# tempeh_Hat.net
KiCad netlist of a schematic drawn in EAGLE
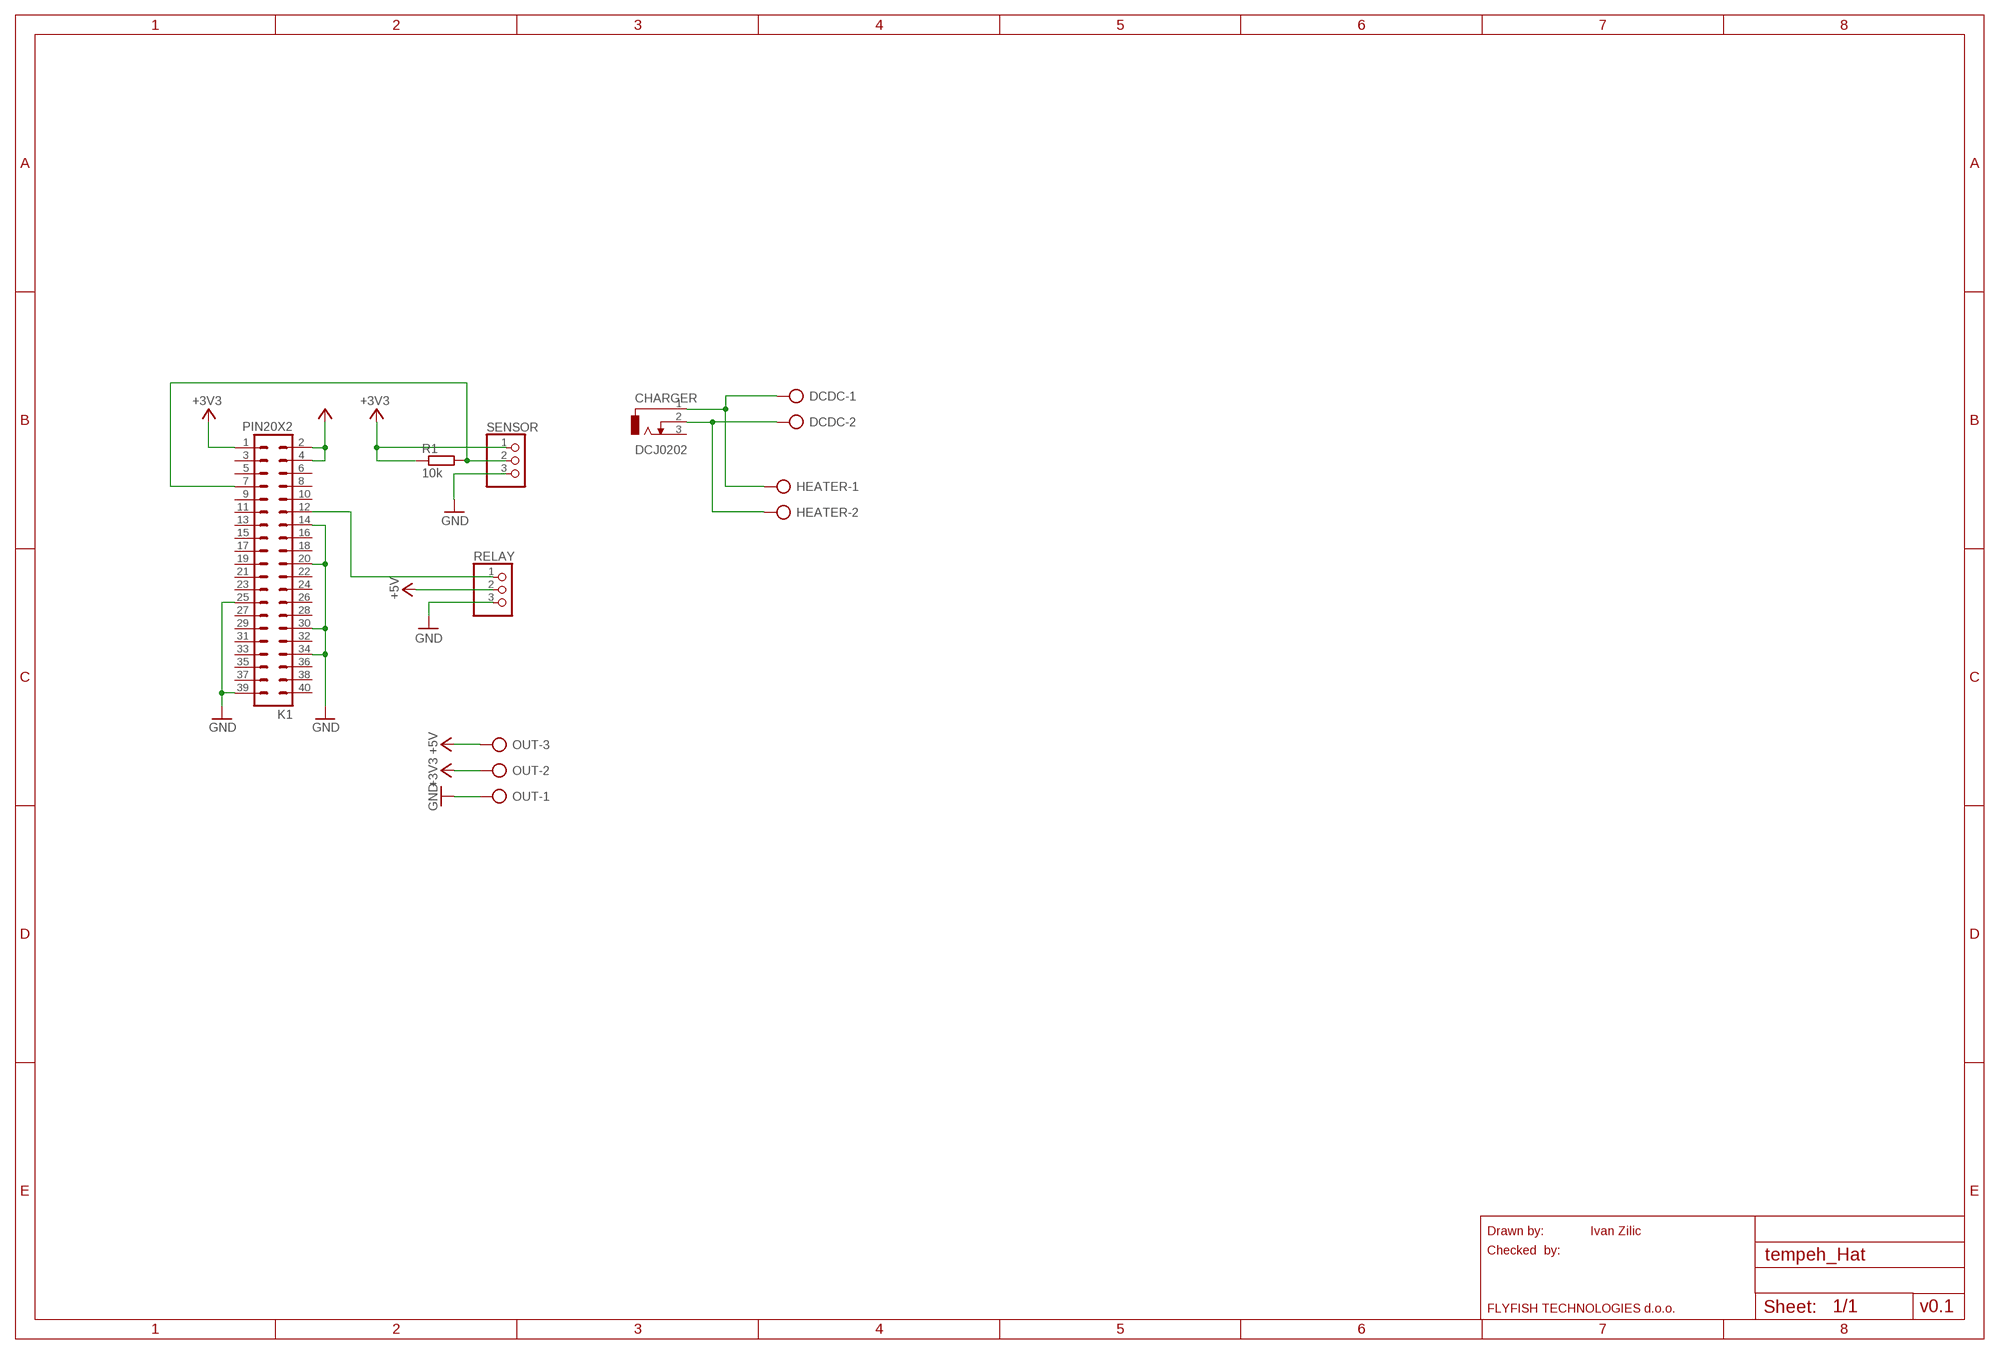
[diagram p0: schematic, sheet 1]

(export (version "E")
  (design (tool "Eeschema 10.0.6"))
  (components
    (comp (ref "CHARGER")
      (value "DCJ0202")
      (footprint "eagle-import:DCJ0202")
      (libsource (lib "eagle-import") (part "DCJ0202"))
    )
    (comp (ref "DCDC")
      (value "AK300/2")
      (footprint "eagle-import:AK300_2")
      (libsource (lib "eagle-import") (part "AK300/2"))
    )
    (comp (ref "HEATER")
      (value "AK300/2")
      (footprint "eagle-import:AK300_2")
      (libsource (lib "eagle-import") (part "AK300/2"))
    )
    (comp (ref "K1")
      (value "PIN20X2")
      (footprint "eagle-import:PIN_20X2")
      (libsource (lib "eagle-import") (part "PIN20X2"))
    )
    (comp (ref "OUT")
      (value "AK300/3")
      (footprint "eagle-import:AK300_3")
      (libsource (lib "eagle-import") (part "AK300/3"))
    )
    (comp (ref "R1")
      (value "10k")
      (footprint "eagle-import:0204_7")
      (libsource (lib "eagle-import") (part "R-EU_0204/7"))
    )
    (comp (ref "RELAY")
      (value "PINHD-1X3")
      (footprint "eagle-import:1X03")
      (libsource (lib "eagle-import") (part "PINHD-1X3"))
    )
    (comp (ref "SENSOR")
      (value "PINHD-1X3")
      (footprint "eagle-import:1X03")
      (libsource (lib "eagle-import") (part "PINHD-1X3"))
    )
  )
  (nets
    (net (code "1") (name "+3V3") (class "Default")
      (node (ref "K1") (pin "1") (pinfunction "1_1") (pintype "passive"))
      (node (ref "OUT") (pin "2") (pinfunction "KL_2") (pintype "passive"))
      (node (ref "R1") (pin "1") (pinfunction "1_1") (pintype "passive"))
      (node (ref "SENSOR") (pin "1") (pinfunction "1_1") (pintype "passive"))
    )
    (net (code "2") (name "+5V") (class "Default")
      (node (ref "K1") (pin "2") (pinfunction "2_2") (pintype "passive"))
      (node (ref "K1") (pin "4") (pinfunction "4_4") (pintype "passive"))
      (node (ref "OUT") (pin "3") (pinfunction "KL_3") (pintype "passive"))
      (node (ref "RELAY") (pin "2") (pinfunction "2_2") (pintype "passive"))
    )
    (net (code "3") (name "GND") (class "Default")
      (node (ref "K1") (pin "14") (pinfunction "14_14") (pintype "passive"))
      (node (ref "K1") (pin "20") (pinfunction "20_20") (pintype "passive"))
      (node (ref "K1") (pin "25") (pinfunction "25_25") (pintype "passive"))
      (node (ref "K1") (pin "30") (pinfunction "30_30") (pintype "passive"))
      (node (ref "K1") (pin "34") (pinfunction "34_34") (pintype "passive"))
      (node (ref "K1") (pin "39") (pinfunction "39_39") (pintype "passive"))
      (node (ref "OUT") (pin "1") (pinfunction "KL_1") (pintype "passive"))
      (node (ref "RELAY") (pin "3") (pinfunction "3_3") (pintype "passive"))
      (node (ref "SENSOR") (pin "3") (pinfunction "3_3") (pintype "passive"))
    )
    (net (code "4") (name "Net-(DCDCA-KL)") (class "Default")
      (node (ref "CHARGER") (pin "1") (pinfunction "1_1") (pintype "passive"))
      (node (ref "DCDC") (pin "1") (pinfunction "KL_1") (pintype "passive"))
      (node (ref "HEATER") (pin "1") (pinfunction "KL_1") (pintype "passive"))
    )
    (net (code "5") (name "Net-(DCDCB-KL)") (class "Default")
      (node (ref "CHARGER") (pin "2") (pinfunction "2_2") (pintype "passive"))
      (node (ref "DCDC") (pin "2") (pinfunction "KL_2") (pintype "passive"))
      (node (ref "HEATER") (pin "2") (pinfunction "KL_2") (pintype "passive"))
    )
    (net (code "6") (name "Net-(K1-Pad7)") (class "Default")
      (node (ref "K1") (pin "7") (pinfunction "7_7") (pintype "passive"))
      (node (ref "R1") (pin "2") (pinfunction "2_2") (pintype "passive"))
      (node (ref "SENSOR") (pin "2") (pinfunction "2_2") (pintype "passive"))
    )
    (net (code "7") (name "Net-(K1-Pad12)") (class "Default")
      (node (ref "K1") (pin "12") (pinfunction "12_12") (pintype "passive"))
      (node (ref "RELAY") (pin "1") (pinfunction "1_1") (pintype "passive"))
    )
    (net (code "8") (name "unconnected-(CHARGER-Pad3)") (class "Default")
      (node (ref "CHARGER") (pin "3") (pinfunction "3_3") (pintype "passive"))
    )
    (net (code "9") (name "unconnected-(K1-Pad3)") (class "Default")
      (node (ref "K1") (pin "3") (pinfunction "3_3") (pintype "passive"))
    )
    (net (code "10") (name "unconnected-(K1-Pad5)") (class "Default")
      (node (ref "K1") (pin "5") (pinfunction "5_5") (pintype "passive"))
    )
    (net (code "11") (name "unconnected-(K1-Pad6)") (class "Default")
      (node (ref "K1") (pin "6") (pinfunction "6_6") (pintype "passive"))
    )
    (net (code "12") (name "unconnected-(K1-Pad8)") (class "Default")
      (node (ref "K1") (pin "8") (pinfunction "8_8") (pintype "passive"))
    )
    (net (code "13") (name "unconnected-(K1-Pad9)") (class "Default")
      (node (ref "K1") (pin "9") (pinfunction "9_9") (pintype "passive"))
    )
    (net (code "14") (name "unconnected-(K1-Pad10)") (class "Default")
      (node (ref "K1") (pin "10") (pinfunction "10_10") (pintype "passive"))
    )
    (net (code "15") (name "unconnected-(K1-Pad11)") (class "Default")
      (node (ref "K1") (pin "11") (pinfunction "11_11") (pintype "passive"))
    )
    (net (code "16") (name "unconnected-(K1-Pad13)") (class "Default")
      (node (ref "K1") (pin "13") (pinfunction "13_13") (pintype "passive"))
    )
    (net (code "17") (name "unconnected-(K1-Pad15)") (class "Default")
      (node (ref "K1") (pin "15") (pinfunction "15_15") (pintype "passive"))
    )
    (net (code "18") (name "unconnected-(K1-Pad16)") (class "Default")
      (node (ref "K1") (pin "16") (pinfunction "16_16") (pintype "passive"))
    )
    (net (code "19") (name "unconnected-(K1-Pad17)") (class "Default")
      (node (ref "K1") (pin "17") (pinfunction "17_17") (pintype "passive"))
    )
    (net (code "20") (name "unconnected-(K1-Pad18)") (class "Default")
      (node (ref "K1") (pin "18") (pinfunction "18_18") (pintype "passive"))
    )
    (net (code "21") (name "unconnected-(K1-Pad19)") (class "Default")
      (node (ref "K1") (pin "19") (pinfunction "19_19") (pintype "passive"))
    )
    (net (code "22") (name "unconnected-(K1-Pad21)") (class "Default")
      (node (ref "K1") (pin "21") (pinfunction "21_21") (pintype "passive"))
    )
    (net (code "23") (name "unconnected-(K1-Pad22)") (class "Default")
      (node (ref "K1") (pin "22") (pinfunction "22_22") (pintype "passive"))
    )
    (net (code "24") (name "unconnected-(K1-Pad23)") (class "Default")
      (node (ref "K1") (pin "23") (pinfunction "23_23") (pintype "passive"))
    )
    (net (code "25") (name "unconnected-(K1-Pad24)") (class "Default")
      (node (ref "K1") (pin "24") (pinfunction "24_24") (pintype "passive"))
    )
    (net (code "26") (name "unconnected-(K1-Pad26)") (class "Default")
      (node (ref "K1") (pin "26") (pinfunction "26_26") (pintype "passive"))
    )
    (net (code "27") (name "unconnected-(K1-Pad27)") (class "Default")
      (node (ref "K1") (pin "27") (pinfunction "27_27") (pintype "passive"))
    )
    (net (code "28") (name "unconnected-(K1-Pad28)") (class "Default")
      (node (ref "K1") (pin "28") (pinfunction "28_28") (pintype "passive"))
    )
    (net (code "29") (name "unconnected-(K1-Pad29)") (class "Default")
      (node (ref "K1") (pin "29") (pinfunction "29_29") (pintype "passive"))
    )
    (net (code "30") (name "unconnected-(K1-Pad31)") (class "Default")
      (node (ref "K1") (pin "31") (pinfunction "31_31") (pintype "passive"))
    )
    (net (code "31") (name "unconnected-(K1-Pad32)") (class "Default")
      (node (ref "K1") (pin "32") (pinfunction "32_32") (pintype "passive"))
    )
    (net (code "32") (name "unconnected-(K1-Pad33)") (class "Default")
      (node (ref "K1") (pin "33") (pinfunction "33_33") (pintype "passive"))
    )
    (net (code "33") (name "unconnected-(K1-Pad35)") (class "Default")
      (node (ref "K1") (pin "35") (pinfunction "35_35") (pintype "passive"))
    )
    (net (code "34") (name "unconnected-(K1-Pad36)") (class "Default")
      (node (ref "K1") (pin "36") (pinfunction "36_36") (pintype "passive"))
    )
    (net (code "35") (name "unconnected-(K1-Pad37)") (class "Default")
      (node (ref "K1") (pin "37") (pinfunction "37_37") (pintype "passive"))
    )
    (net (code "36") (name "unconnected-(K1-Pad38)") (class "Default")
      (node (ref "K1") (pin "38") (pinfunction "38_38") (pintype "passive"))
    )
    (net (code "37") (name "unconnected-(K1-Pad40)") (class "Default")
      (node (ref "K1") (pin "40") (pinfunction "40_40") (pintype "passive"))
    )
  )
)
